# SRAM_OneNAND.net
KiCad netlist of a schematic drawn in Altium Designer
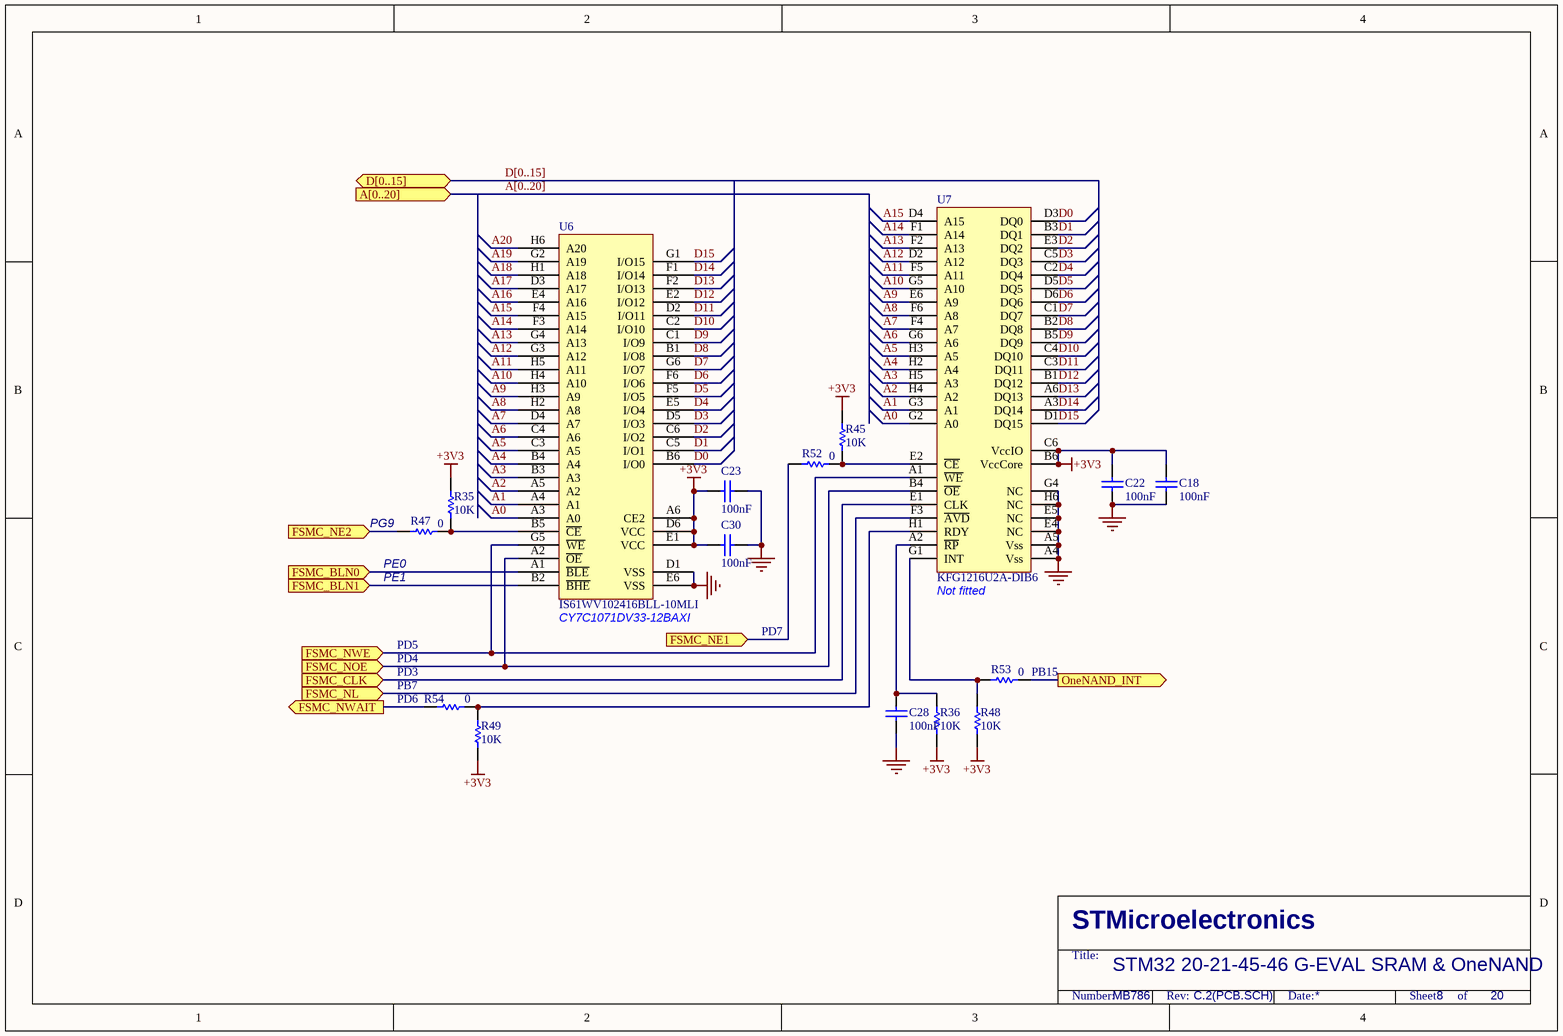
[diagram p0: SRAM&OneNAND.SchDoc]

(export (version "E")
  (design (tool "Eeschema 10.0.6"))
  (components
    (comp (ref "C18")
      (value "100nF")
      (footprint "0402C")
      (description "Capacitor")
      (fields (field (name "PUBLISHER") "Altium Limited"))
      (libsource (lib "Miscellaneous Devices") (part "cap"))
    )
    (comp (ref "C22")
      (value "100nF")
      (footprint "0402C")
      (description "Capacitor")
      (fields (field (name "PUBLISHER") "Altium Limited"))
      (libsource (lib "Miscellaneous Devices") (part "cap"))
    )
    (comp (ref "C23")
      (value "100nF")
      (footprint "0402C")
      (description "Capacitor")
      (fields (field (name "PUBLISHER") "Altium Limited"))
      (libsource (lib "Miscellaneous Devices") (part "cap"))
    )
    (comp (ref "C28")
      (value "100nF")
      (footprint "0402C")
      (description "Capacitor")
      (fields (field (name "PUBLISHER") "Altium Limited"))
      (libsource (lib "Miscellaneous Devices") (part "cap"))
    )
    (comp (ref "C30")
      (value "100nF")
      (footprint "0402C")
      (description "Capacitor")
      (fields (field (name "PUBLISHER") "Altium Limited"))
      (libsource (lib "Miscellaneous Devices") (part "cap"))
    )
    (comp (ref "R35")
      (value "10K")
      (footprint "0402R")
      (description "Resistor")
      (fields (field (name "PUBLISHER") "Altium Limited"))
      (libsource (lib "Miscellaneous Devices") (part "Res1"))
    )
    (comp (ref "R36")
      (value "10K")
      (footprint "0402R")
      (description "Resistor")
      (fields (field (name "PUBLISHER") "Altium Limited"))
      (libsource (lib "Miscellaneous Devices") (part "Res1"))
    )
    (comp (ref "R45")
      (value "10K")
      (footprint "0402R")
      (description "Resistor")
      (fields (field (name "PUBLISHER") "Altium Limited"))
      (libsource (lib "Miscellaneous Devices") (part "Res1"))
    )
    (comp (ref "R47")
      (value "0")
      (footprint "0603R")
      (description "Resistor")
      (fields (field (name "PUBLISHER") "Altium Limited"))
      (libsource (lib "Miscellaneous Devices") (part "Res1"))
    )
    (comp (ref "R48")
      (value "10K")
      (footprint "0402R")
      (description "Resistor")
      (fields (field (name "PUBLISHER") "Altium Limited"))
      (libsource (lib "Miscellaneous Devices") (part "Res1"))
    )
    (comp (ref "R49")
      (value "10K")
      (footprint "0402R")
      (description "Resistor")
      (fields (field (name "PUBLISHER") "Altium Limited"))
      (libsource (lib "Miscellaneous Devices") (part "Res1"))
    )
    (comp (ref "R52")
      (value "0")
      (footprint "0603R")
      (description "Resistor")
      (fields (field (name "PUBLISHER") "Altium Limited"))
      (libsource (lib "Miscellaneous Devices") (part "Res1"))
    )
    (comp (ref "R53")
      (value "0")
      (footprint "0603R")
      (description "Resistor")
      (fields (field (name "PUBLISHER") "Altium Limited"))
      (libsource (lib "Miscellaneous Devices") (part "Res1"))
    )
    (comp (ref "R54")
      (value "0")
      (footprint "0603R")
      (description "Resistor")
      (fields (field (name "PUBLISHER") "Altium Limited"))
      (libsource (lib "Miscellaneous Devices") (part "Res1"))
    )
    (comp (ref "U6")
      (value "IS61WV102416BLL-10MLI")
      (footprint "FBGA48(9*11)")
      (libsource (lib "MB901") (part "IS61WV102416BLL-10MLI"))
    )
    (comp (ref "U7")
      (value "KFG1216U2A-DIB6")
      (footprint "FBGA63(9.5*12)")
      (libsource (lib "MB786") (part "KFG1216U2A-DIB6"))
    )
  )
  (nets
    (net (code "1") (name "+3V3") (class "Default")
      (node (ref "C18") (pin "1") (pinfunction "1_1") (pintype "passive"))
      (node (ref "C22") (pin "1") (pinfunction "1_1") (pintype "passive"))
      (node (ref "C23") (pin "2") (pinfunction "2_2") (pintype "passive"))
      (node (ref "C30") (pin "2") (pinfunction "2_2") (pintype "passive"))
      (node (ref "R35") (pin "2") (pinfunction "2_2") (pintype "passive"))
      (node (ref "R36") (pin "1") (pinfunction "1_1") (pintype "passive"))
      (node (ref "R45") (pin "2") (pinfunction "2_2") (pintype "passive"))
      (node (ref "R48") (pin "1") (pinfunction "1_1") (pintype "passive"))
      (node (ref "R49") (pin "1") (pinfunction "1_1") (pintype "passive"))
      (node (ref "U6") (pin "A6") (pinfunction "CE2_A6") (pintype "passive"))
      (node (ref "U6") (pin "D6") (pinfunction "VCC_D6") (pintype "passive"))
      (node (ref "U6") (pin "E1") (pinfunction "VCC_E1") (pintype "passive"))
      (node (ref "U7") (pin "B6") (pinfunction "VccCore_B6") (pintype "passive"))
      (node (ref "U7") (pin "C6") (pinfunction "VccIO_C6") (pintype "passive"))
    )
    (net (code "2") (name "/A0") (class "Default")
      (node (ref "U6") (pin "A3") (pinfunction "A0_A3") (pintype "passive"))
      (node (ref "U7") (pin "G2") (pinfunction "A0_G2") (pintype "passive"))
    )
    (net (code "3") (name "/A1") (class "Default")
      (node (ref "U6") (pin "A4") (pinfunction "A1_A4") (pintype "passive"))
      (node (ref "U7") (pin "G3") (pinfunction "A1_G3") (pintype "passive"))
    )
    (net (code "4") (name "/A2") (class "Default")
      (node (ref "U6") (pin "A5") (pinfunction "A2_A5") (pintype "passive"))
      (node (ref "U7") (pin "H4") (pinfunction "A2_H4") (pintype "passive"))
    )
    (net (code "5") (name "/A3") (class "Default")
      (node (ref "U6") (pin "B3") (pinfunction "A3_B3") (pintype "passive"))
      (node (ref "U7") (pin "H5") (pinfunction "A3_H5") (pintype "passive"))
    )
    (net (code "6") (name "/A4") (class "Default")
      (node (ref "U6") (pin "B4") (pinfunction "A4_B4") (pintype "passive"))
      (node (ref "U7") (pin "H2") (pinfunction "A4_H2") (pintype "passive"))
    )
    (net (code "7") (name "/A5") (class "Default")
      (node (ref "U6") (pin "C3") (pinfunction "A5_C3") (pintype "passive"))
      (node (ref "U7") (pin "H3") (pinfunction "A5_H3") (pintype "passive"))
    )
    (net (code "8") (name "/A6") (class "Default")
      (node (ref "U6") (pin "C4") (pinfunction "A6_C4") (pintype "passive"))
      (node (ref "U7") (pin "G6") (pinfunction "A6_G6") (pintype "passive"))
    )
    (net (code "9") (name "/A7") (class "Default")
      (node (ref "U6") (pin "D4") (pinfunction "A7_D4") (pintype "passive"))
      (node (ref "U7") (pin "F4") (pinfunction "A7_F4") (pintype "passive"))
    )
    (net (code "10") (name "/A8") (class "Default")
      (node (ref "U6") (pin "H2") (pinfunction "A8_H2") (pintype "passive"))
      (node (ref "U7") (pin "F6") (pinfunction "A8_F6") (pintype "passive"))
    )
    (net (code "11") (name "/A9") (class "Default")
      (node (ref "U6") (pin "H3") (pinfunction "A9_H3") (pintype "passive"))
      (node (ref "U7") (pin "E6") (pinfunction "A9_E6") (pintype "passive"))
    )
    (net (code "12") (name "/A10") (class "Default")
      (node (ref "U6") (pin "H4") (pinfunction "A10_H4") (pintype "passive"))
      (node (ref "U7") (pin "G5") (pinfunction "A10_G5") (pintype "passive"))
    )
    (net (code "13") (name "/A11") (class "Default")
      (node (ref "U6") (pin "H5") (pinfunction "A11_H5") (pintype "passive"))
      (node (ref "U7") (pin "F5") (pinfunction "A11_F5") (pintype "passive"))
    )
    (net (code "14") (name "/A12") (class "Default")
      (node (ref "U6") (pin "G3") (pinfunction "A12_G3") (pintype "passive"))
      (node (ref "U7") (pin "D2") (pinfunction "A12_D2") (pintype "passive"))
    )
    (net (code "15") (name "/A13") (class "Default")
      (node (ref "U6") (pin "G4") (pinfunction "A13_G4") (pintype "passive"))
      (node (ref "U7") (pin "F2") (pinfunction "A13_F2") (pintype "passive"))
    )
    (net (code "16") (name "/A14") (class "Default")
      (node (ref "U6") (pin "F3") (pinfunction "A14_F3") (pintype "passive"))
      (node (ref "U7") (pin "F1") (pinfunction "A14_F1") (pintype "passive"))
    )
    (net (code "17") (name "/A15") (class "Default")
      (node (ref "U6") (pin "F4") (pinfunction "A15_F4") (pintype "passive"))
      (node (ref "U7") (pin "D4") (pinfunction "A15_D4") (pintype "passive"))
    )
    (net (code "18") (name "/A16") (class "Default")
      (node (ref "U6") (pin "E4") (pinfunction "A16_E4") (pintype "passive"))
    )
    (net (code "19") (name "/A17") (class "Default")
      (node (ref "U6") (pin "D3") (pinfunction "A17_D3") (pintype "passive"))
    )
    (net (code "20") (name "/A18") (class "Default")
      (node (ref "U6") (pin "H1") (pinfunction "A18_H1") (pintype "passive"))
    )
    (net (code "21") (name "/A19") (class "Default")
      (node (ref "U6") (pin "G2") (pinfunction "A19_G2") (pintype "passive"))
    )
    (net (code "22") (name "/A20") (class "Default")
      (node (ref "U6") (pin "H6") (pinfunction "A20_H6") (pintype "passive"))
    )
    (net (code "24") (name "/D0") (class "Default")
      (node (ref "U6") (pin "B6") (pinfunction "I/O0_B6") (pintype "passive"))
      (node (ref "U7") (pin "D3") (pinfunction "DQ0_D3") (pintype "passive"))
    )
    (net (code "25") (name "/D1") (class "Default")
      (node (ref "U6") (pin "C5") (pinfunction "I/O1_C5") (pintype "passive"))
      (node (ref "U7") (pin "B3") (pinfunction "DQ1_B3") (pintype "passive"))
    )
    (net (code "26") (name "/D2") (class "Default")
      (node (ref "U6") (pin "C6") (pinfunction "I/O2_C6") (pintype "passive"))
      (node (ref "U7") (pin "E3") (pinfunction "DQ2_E3") (pintype "passive"))
    )
    (net (code "27") (name "/D3") (class "Default")
      (node (ref "U6") (pin "D5") (pinfunction "I/O3_D5") (pintype "passive"))
      (node (ref "U7") (pin "C5") (pinfunction "DQ3_C5") (pintype "passive"))
    )
    (net (code "28") (name "/D4") (class "Default")
      (node (ref "U6") (pin "E5") (pinfunction "I/O4_E5") (pintype "passive"))
      (node (ref "U7") (pin "C2") (pinfunction "DQ4_C2") (pintype "passive"))
    )
    (net (code "29") (name "/D5") (class "Default")
      (node (ref "U6") (pin "F5") (pinfunction "I/O5_F5") (pintype "passive"))
      (node (ref "U7") (pin "D5") (pinfunction "DQ5_D5") (pintype "passive"))
    )
    (net (code "30") (name "/D6") (class "Default")
      (node (ref "U6") (pin "F6") (pinfunction "I/O6_F6") (pintype "passive"))
      (node (ref "U7") (pin "D6") (pinfunction "DQ6_D6") (pintype "passive"))
    )
    (net (code "31") (name "/D7") (class "Default")
      (node (ref "U6") (pin "G6") (pinfunction "I/O7_G6") (pintype "passive"))
      (node (ref "U7") (pin "C1") (pinfunction "DQ7_C1") (pintype "passive"))
    )
    (net (code "32") (name "/D8") (class "Default")
      (node (ref "U6") (pin "B1") (pinfunction "I/O8_B1") (pintype "passive"))
      (node (ref "U7") (pin "B2") (pinfunction "DQ8_B2") (pintype "passive"))
    )
    (net (code "33") (name "/D9") (class "Default")
      (node (ref "U6") (pin "C1") (pinfunction "I/O9_C1") (pintype "passive"))
      (node (ref "U7") (pin "B5") (pinfunction "DQ9_B5") (pintype "passive"))
    )
    (net (code "34") (name "/D10") (class "Default")
      (node (ref "U6") (pin "C2") (pinfunction "I/O10_C2") (pintype "passive"))
      (node (ref "U7") (pin "C4") (pinfunction "DQ10_C4") (pintype "passive"))
    )
    (net (code "35") (name "/D11") (class "Default")
      (node (ref "U6") (pin "D2") (pinfunction "I/O11_D2") (pintype "passive"))
      (node (ref "U7") (pin "C3") (pinfunction "DQ11_C3") (pintype "passive"))
    )
    (net (code "36") (name "/D12") (class "Default")
      (node (ref "U6") (pin "E2") (pinfunction "I/O12_E2") (pintype "passive"))
      (node (ref "U7") (pin "B1") (pinfunction "DQ12_B1") (pintype "passive"))
    )
    (net (code "37") (name "/D13") (class "Default")
      (node (ref "U6") (pin "F2") (pinfunction "I/O13_F2") (pintype "passive"))
      (node (ref "U7") (pin "A6") (pinfunction "DQ13_A6") (pintype "passive"))
    )
    (net (code "38") (name "/D14") (class "Default")
      (node (ref "U6") (pin "F1") (pinfunction "I/O14_F1") (pintype "passive"))
      (node (ref "U7") (pin "A3") (pinfunction "DQ14_A3") (pintype "passive"))
    )
    (net (code "39") (name "/D15") (class "Default")
      (node (ref "U6") (pin "G1") (pinfunction "I/O15_G1") (pintype "passive"))
      (node (ref "U7") (pin "D1") (pinfunction "DQ15_D1") (pintype "passive"))
    )
    (net (code "41") (name "/FSMC_BLN0") (class "Default")
      (node (ref "U6") (pin "A1") (pinfunction "~{BLE}_A1") (pintype "passive"))
    )
    (net (code "42") (name "/FSMC_BLN1") (class "Default")
      (node (ref "U6") (pin "B2") (pinfunction "~{BHE}_B2") (pintype "passive"))
    )
    (net (code "43") (name "/FSMC_CLK") (class "Default")
      (node (ref "U7") (pin "E1") (pinfunction "CLK_E1") (pintype "passive"))
    )
    (net (code "44") (name "/FSMC_NE1") (class "Default")
      (node (ref "R52") (pin "2") (pinfunction "2_2") (pintype "passive"))
    )
    (net (code "45") (name "/FSMC_NE2") (class "Default")
      (node (ref "R47") (pin "2") (pinfunction "2_2") (pintype "passive"))
    )
    (net (code "46") (name "/FSMC_NL") (class "Default")
      (node (ref "U7") (pin "F3") (pinfunction "~{AVD}_F3") (pintype "passive"))
    )
    (net (code "47") (name "/FSMC_NOE") (class "Default")
      (node (ref "U6") (pin "A2") (pinfunction "~{OE}_A2") (pintype "passive"))
      (node (ref "U7") (pin "B4") (pinfunction "~{OE}_B4") (pintype "passive"))
    )
    (net (code "48") (name "/FSMC_NWAIT") (class "Default")
      (node (ref "R54") (pin "2") (pinfunction "2_2") (pintype "passive"))
    )
    (net (code "49") (name "/FSMC_NWE") (class "Default")
      (node (ref "U6") (pin "G5") (pinfunction "~{WE}_G5") (pintype "passive"))
      (node (ref "U7") (pin "A1") (pinfunction "~{WE}_A1") (pintype "passive"))
    )
    (net (code "50") (name "/OneNAND_INT") (class "Default")
      (node (ref "R53") (pin "1") (pinfunction "1_1") (pintype "passive"))
    )
    (net (code "51") (name "GND") (class "Default")
      (node (ref "C18") (pin "2") (pinfunction "2_2") (pintype "passive"))
      (node (ref "C22") (pin "2") (pinfunction "2_2") (pintype "passive"))
      (node (ref "C23") (pin "1") (pinfunction "1_1") (pintype "passive"))
      (node (ref "C28") (pin "1") (pinfunction "1_1") (pintype "passive"))
      (node (ref "C30") (pin "1") (pinfunction "1_1") (pintype "passive"))
      (node (ref "U6") (pin "D1") (pinfunction "VSS_D1") (pintype "passive"))
      (node (ref "U6") (pin "E6") (pinfunction "VSS_E6") (pintype "passive"))
      (node (ref "U7") (pin "A4") (pinfunction "Vss_A4") (pintype "passive"))
      (node (ref "U7") (pin "A5") (pinfunction "Vss_A5") (pintype "passive"))
      (node (ref "U7") (pin "E4") (pinfunction "NC_E4") (pintype "passive"))
      (node (ref "U7") (pin "E5") (pinfunction "NC_E5") (pintype "passive"))
      (node (ref "U7") (pin "G4") (pinfunction "NC_G4") (pintype "passive"))
      (node (ref "U7") (pin "H6") (pinfunction "NC_H6") (pintype "passive"))
    )
    (net (code "52") (name "Net-(U6-~{CE})") (class "Default")
      (node (ref "R35") (pin "1") (pinfunction "1_1") (pintype "passive"))
      (node (ref "R47") (pin "1") (pinfunction "1_1") (pintype "passive"))
      (node (ref "U6") (pin "B5") (pinfunction "~{CE}_B5") (pintype "passive"))
    )
    (net (code "53") (name "Net-(U7-INT)") (class "Default")
      (node (ref "R48") (pin "2") (pinfunction "2_2") (pintype "passive"))
      (node (ref "R53") (pin "2") (pinfunction "2_2") (pintype "passive"))
      (node (ref "U7") (pin "G1") (pinfunction "INT_G1") (pintype "passive"))
    )
    (net (code "54") (name "Net-(U7-RDY)") (class "Default")
      (node (ref "R49") (pin "2") (pinfunction "2_2") (pintype "passive"))
      (node (ref "R54") (pin "1") (pinfunction "1_1") (pintype "passive"))
      (node (ref "U7") (pin "H1") (pinfunction "RDY_H1") (pintype "passive"))
    )
    (net (code "55") (name "Net-(U7-~{CE})") (class "Default")
      (node (ref "R45") (pin "1") (pinfunction "1_1") (pintype "passive"))
      (node (ref "R52") (pin "1") (pinfunction "1_1") (pintype "passive"))
      (node (ref "U7") (pin "E2") (pinfunction "~{CE}_E2") (pintype "passive"))
    )
    (net (code "56") (name "Net-(U7-~{RP})") (class "Default")
      (node (ref "C28") (pin "2") (pinfunction "2_2") (pintype "passive"))
      (node (ref "R36") (pin "2") (pinfunction "2_2") (pintype "passive"))
      (node (ref "U7") (pin "A2") (pinfunction "~{RP}_A2") (pintype "passive"))
    )
  )
)
